# POW_Schematic2.net
KiCad netlist of a schematic drawn in Altium Designer
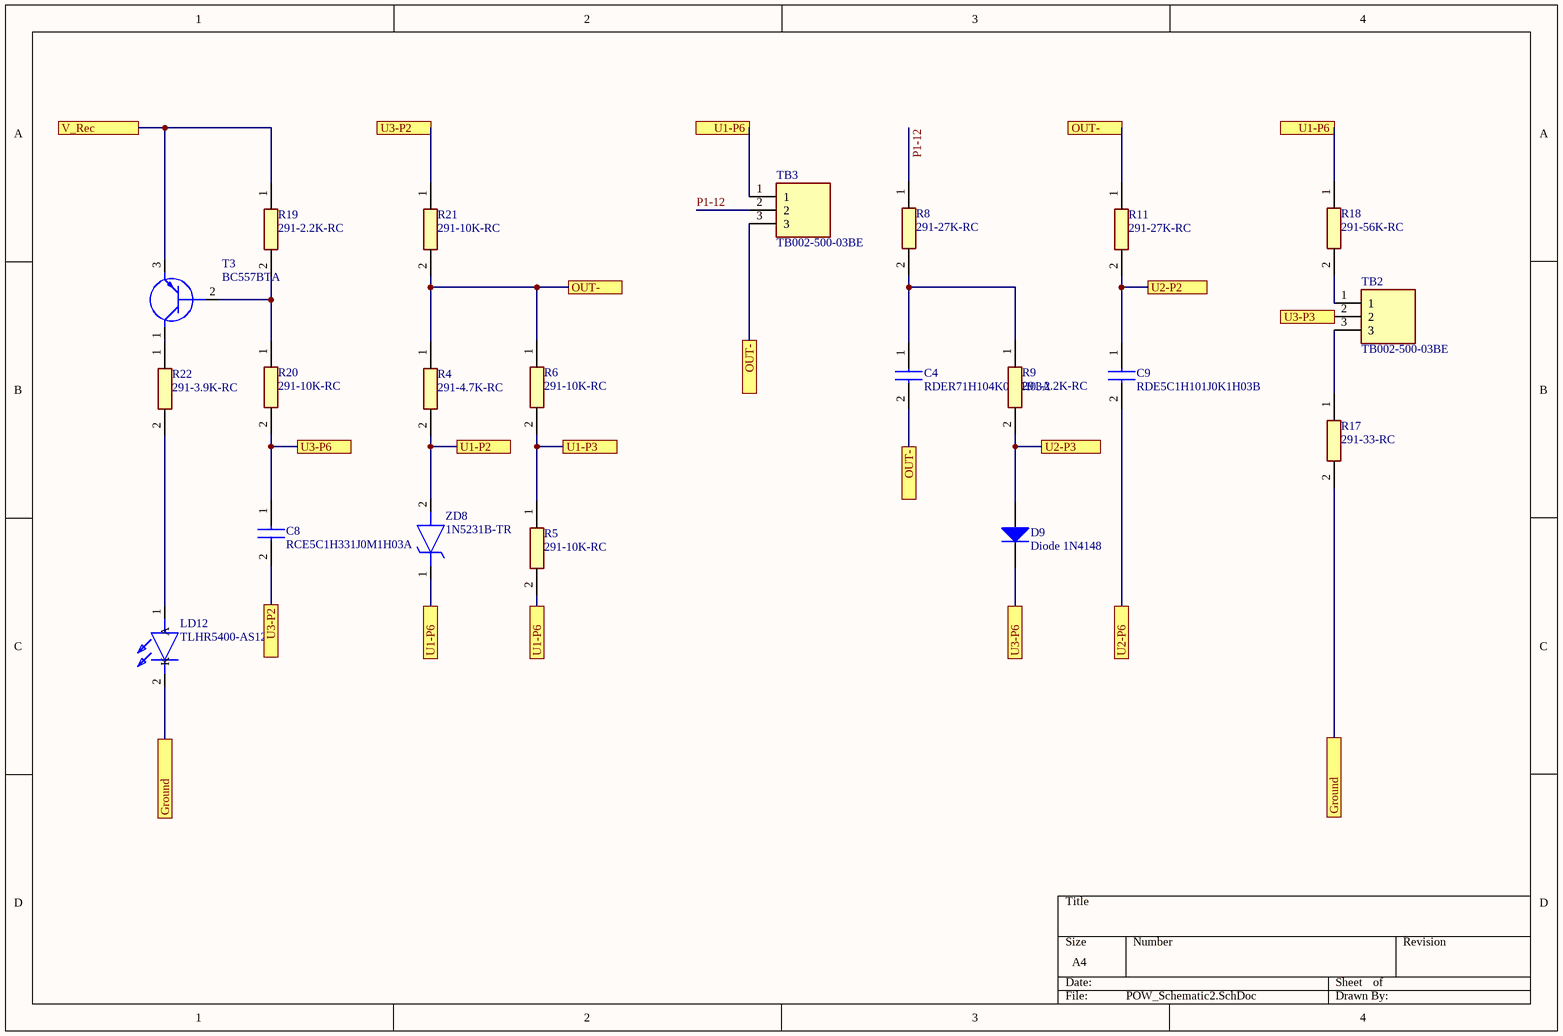
[diagram p0: POW_Schematic2.SchDoc]

(export (version "E")
  (design (tool "Eeschema 10.0.6"))
  (components
    (comp (ref "C4")
      (value "RDER71H104K0S1H03A")
      (footprint "RDE5C1H100J0P1H03B")
      (description "Capacitor")
      (fields (field (name "MOUSER PART NUMBER") "81-RDER71H104K0S1H3A"))
      (libsource (lib "Schlib_POW_HugoHamblok") (part "RDER71H104K0S1H03A"))
    )
    (comp (ref "C8")
      (value "RCE5C1H331J0M1H03A")
      (footprint "PcbLib_POW_HugoHamblok:RCE5C1H100J0A2H03B")
      (description "Capacitor")
      (libsource (lib "Schlib_POW_HugoHamblok") (part "RCE5C1H331J0M1H03A"))
    )
    (comp (ref "C9")
      (value "RDE5C1H101J0K1H03B")
      (footprint "RCE5C1H103J1A2H03B")
      (description "Capacitor")
      (fields (field (name "MOUSER PART NUMBER") "81-RDE5C1H101J0K1H3B"))
      (libsource (lib "Schlib_POW_HugoHamblok") (part "RDE5C1H101J0K1H03B"))
    )
    (comp (ref "D9")
      (value "Diode 1N4148")
      (footprint "DO-35")
      (description "High Conductance Fast Diode")
      (fields (field (name "PUBLISHER") "Altium Limited"))
      (libsource (lib "Miscellaneous Devices") (part "Diode 1N4148"))
    )
    (comp (ref "LD12")
      (value "TLHR5400-AS12Z")
      (footprint "TLHR5400AS12Z")
      (description "LED")
      (fields (field (name "MOUSER PART NUMBER") "78-TLHR5400-AS12Z"))
      (libsource (lib "Schlib_POW_HugoHamblok") (part "TLHR5400-AS12Z"))
    )
    (comp (ref "R4")
      (value "291-4.7K-RC")
      (footprint "291-XXX-RC-Type")
      (libsource (lib "Schlib_POW_HugoHamblok") (part "291-4.7K-RC"))
    )
    (comp (ref "R5")
      (value "291-10K-RC")
      (footprint "291-XXX-RC-Type")
      (libsource (lib "Schlib_POW_HugoHamblok") (part "291-10K-RC"))
    )
    (comp (ref "R6")
      (value "291-10K-RC")
      (footprint "291-XXX-RC-Type")
      (libsource (lib "Schlib_POW_HugoHamblok") (part "291-10K-RC"))
    )
    (comp (ref "R8")
      (value "291-27K-RC")
      (footprint "291-XXX-RC-Type")
      (libsource (lib "Schlib_POW_HugoHamblok") (part "291-27K-RC"))
    )
    (comp (ref "R9")
      (value "291-2.2K-RC")
      (footprint "291-XXX-RC-Type")
      (libsource (lib "Schlib_POW_HugoHamblok") (part "291-2.2K-RC"))
    )
    (comp (ref "R11")
      (value "291-27K-RC")
      (footprint "291-XXX-RC-Type")
      (libsource (lib "Schlib_POW_HugoHamblok") (part "291-27K-RC"))
    )
    (comp (ref "R17")
      (value "291-33-RC")
      (footprint "291-XXX-RC-Type")
      (libsource (lib "Schlib_POW_HugoHamblok") (part "291-33-RC"))
    )
    (comp (ref "R18")
      (value "291-56K-RC")
      (footprint "291-XXX-RC-Type")
      (libsource (lib "Schlib_POW_HugoHamblok") (part "291-56K-RC"))
    )
    (comp (ref "R19")
      (value "291-2.2K-RC")
      (footprint "291-XXX-RC-Type")
      (libsource (lib "Schlib_POW_HugoHamblok") (part "291-2.2K-RC"))
    )
    (comp (ref "R20")
      (value "291-10K-RC")
      (footprint "291-XXX-RC-Type")
      (libsource (lib "Schlib_POW_HugoHamblok") (part "291-10K-RC"))
    )
    (comp (ref "R21")
      (value "291-10K-RC")
      (footprint "291-XXX-RC-Type")
      (libsource (lib "Schlib_POW_HugoHamblok") (part "291-10K-RC"))
    )
    (comp (ref "R22")
      (value "291-3.9K-RC")
      (footprint "291-XXX-RC-Type")
      (libsource (lib "Schlib_POW_HugoHamblok") (part "291-3.9K-RC"))
    )
    (comp (ref "T3")
      (value "BC557BTA")
      (footprint "TO260P419X476X877-3P")
      (description "Transistor BJT PNP")
      (fields (field (name "MOUSER PART NUMBER") "512-BC557BTA") (field (name "RS PART NUMBER") "7613505P"))
      (libsource (lib "Schlib_POW_HugoHamblok") (part "BC557BTA"))
    )
    (comp (ref "TB2")
      (value "TB002-500-03BE")
      (footprint "SHDR3W100P0X500_1X3_1500X760X1000P")
      (description "Connector")
      (fields (field (name "MOUSER PART NUMBER") "490-TB002-500-03BE"))
      (libsource (lib "Schlib_POW_HugoHamblok") (part "TB002-500-03BE"))
    )
    (comp (ref "TB3")
      (value "TB002-500-03BE")
      (footprint "SHDR3W100P0X500_1X3_1500X760X1000P")
      (description "Connector")
      (fields (field (name "MOUSER PART NUMBER") "490-TB002-500-03BE"))
      (libsource (lib "Schlib_POW_HugoHamblok") (part "TB002-500-03BE"))
    )
    (comp (ref "ZD8")
      (value "1N5231B-TR")
      (footprint "DIOAD990W55L350D160")
      (description "Zener Diode")
      (fields (field (name "MOUSER PART NUMBER") "78-1N5231B") (field (name "RS PART NUMBER") "8115967P"))
      (libsource (lib "Schlib_POW_HugoHamblok") (part "1N5231B-TR"))
    )
  )
  (nets
    (net (code "1") (name "/Ground") (class "Default")
      (node (ref "LD12") (pin "2") (pinfunction "K_2") (pintype "passive"))
      (node (ref "R17") (pin "2") (pinfunction "2_2") (pintype "passive"))
    )
    (net (code "2") (name "/OUT-") (class "Default")
      (node (ref "C4") (pin "2") (pinfunction "2_2") (pintype "passive"))
      (node (ref "R11") (pin "1") (pinfunction "1_1") (pintype "passive"))
      (node (ref "R21") (pin "2") (pinfunction "2_2") (pintype "passive"))
      (node (ref "R4") (pin "1") (pinfunction "1_1") (pintype "passive"))
      (node (ref "R6") (pin "1") (pinfunction "1_1") (pintype "passive"))
      (node (ref "TB3") (pin "3") (pinfunction "3_3") (pintype "passive"))
    )
    (net (code "3") (name "/P1-12") (class "Default")
      (node (ref "R8") (pin "1") (pinfunction "1_1") (pintype "passive"))
      (node (ref "TB3") (pin "2") (pinfunction "2_2") (pintype "passive"))
    )
    (net (code "4") (name "/U1-P2") (class "Default")
      (node (ref "R4") (pin "2") (pinfunction "2_2") (pintype "passive"))
      (node (ref "ZD8") (pin "2") (pinfunction "A_2") (pintype "passive"))
    )
    (net (code "5") (name "/U1-P3") (class "Default")
      (node (ref "R5") (pin "1") (pinfunction "1_1") (pintype "passive"))
      (node (ref "R6") (pin "2") (pinfunction "2_2") (pintype "passive"))
    )
    (net (code "6") (name "/U1-P6") (class "Default")
      (node (ref "R18") (pin "1") (pinfunction "1_1") (pintype "passive"))
      (node (ref "R5") (pin "2") (pinfunction "2_2") (pintype "passive"))
      (node (ref "TB3") (pin "1") (pinfunction "1_1") (pintype "passive"))
      (node (ref "ZD8") (pin "1") (pinfunction "K_1") (pintype "passive"))
    )
    (net (code "7") (name "/U2-P2") (class "Default")
      (node (ref "C9") (pin "1") (pinfunction "1_1") (pintype "passive"))
      (node (ref "R11") (pin "2") (pinfunction "2_2") (pintype "passive"))
    )
    (net (code "8") (name "/U2-P3") (class "Default")
      (node (ref "D9") (pin "1") (pinfunction "A_1") (pintype "passive"))
      (node (ref "R9") (pin "2") (pinfunction "2_2") (pintype "passive"))
    )
    (net (code "9") (name "/U2-P6") (class "Default")
      (node (ref "C9") (pin "2") (pinfunction "2_2") (pintype "passive"))
    )
    (net (code "10") (name "/U3-P2") (class "Default")
      (node (ref "C8") (pin "2") (pinfunction "2_2") (pintype "passive"))
      (node (ref "R21") (pin "1") (pinfunction "1_1") (pintype "passive"))
    )
    (net (code "11") (name "/U3-P3") (class "Default")
      (node (ref "TB2") (pin "2") (pinfunction "2_2") (pintype "passive"))
    )
    (net (code "12") (name "/U3-P6") (class "Default")
      (node (ref "C8") (pin "1") (pinfunction "1_1") (pintype "passive"))
      (node (ref "D9") (pin "2") (pinfunction "K_2") (pintype "passive"))
      (node (ref "R20") (pin "2") (pinfunction "2_2") (pintype "passive"))
    )
    (net (code "13") (name "/V_Rec") (class "Default")
      (node (ref "R19") (pin "1") (pinfunction "1_1") (pintype "passive"))
      (node (ref "T3") (pin "3") (pinfunction "E_3") (pintype "passive"))
    )
    (net (code "14") (name "Net-(C4-Pad1)") (class "Default")
      (node (ref "C4") (pin "1") (pinfunction "1_1") (pintype "passive"))
      (node (ref "R8") (pin "2") (pinfunction "2_2") (pintype "passive"))
      (node (ref "R9") (pin "1") (pinfunction "1_1") (pintype "passive"))
    )
    (net (code "15") (name "Net-(LD12-A)") (class "Default")
      (node (ref "LD12") (pin "1") (pinfunction "A_1") (pintype "passive"))
      (node (ref "R22") (pin "2") (pinfunction "2_2") (pintype "passive"))
    )
    (net (code "16") (name "Net-(R17-Pad1)") (class "Default")
      (node (ref "R17") (pin "1") (pinfunction "1_1") (pintype "passive"))
      (node (ref "TB2") (pin "3") (pinfunction "3_3") (pintype "passive"))
    )
    (net (code "17") (name "Net-(R18-Pad2)") (class "Default")
      (node (ref "R18") (pin "2") (pinfunction "2_2") (pintype "passive"))
      (node (ref "TB2") (pin "1") (pinfunction "1_1") (pintype "passive"))
    )
    (net (code "18") (name "Net-(T3-B)") (class "Default")
      (node (ref "R19") (pin "2") (pinfunction "2_2") (pintype "passive"))
      (node (ref "R20") (pin "1") (pinfunction "1_1") (pintype "passive"))
      (node (ref "T3") (pin "2") (pinfunction "B_2") (pintype "passive"))
    )
    (net (code "19") (name "Net-(T3-C)") (class "Default")
      (node (ref "R22") (pin "1") (pinfunction "1_1") (pintype "passive"))
      (node (ref "T3") (pin "1") (pinfunction "C_1") (pintype "passive"))
    )
  )
)
